# Beetech_NanoEvery.net
KiCad netlist of a schematic drawn in Altium Designer
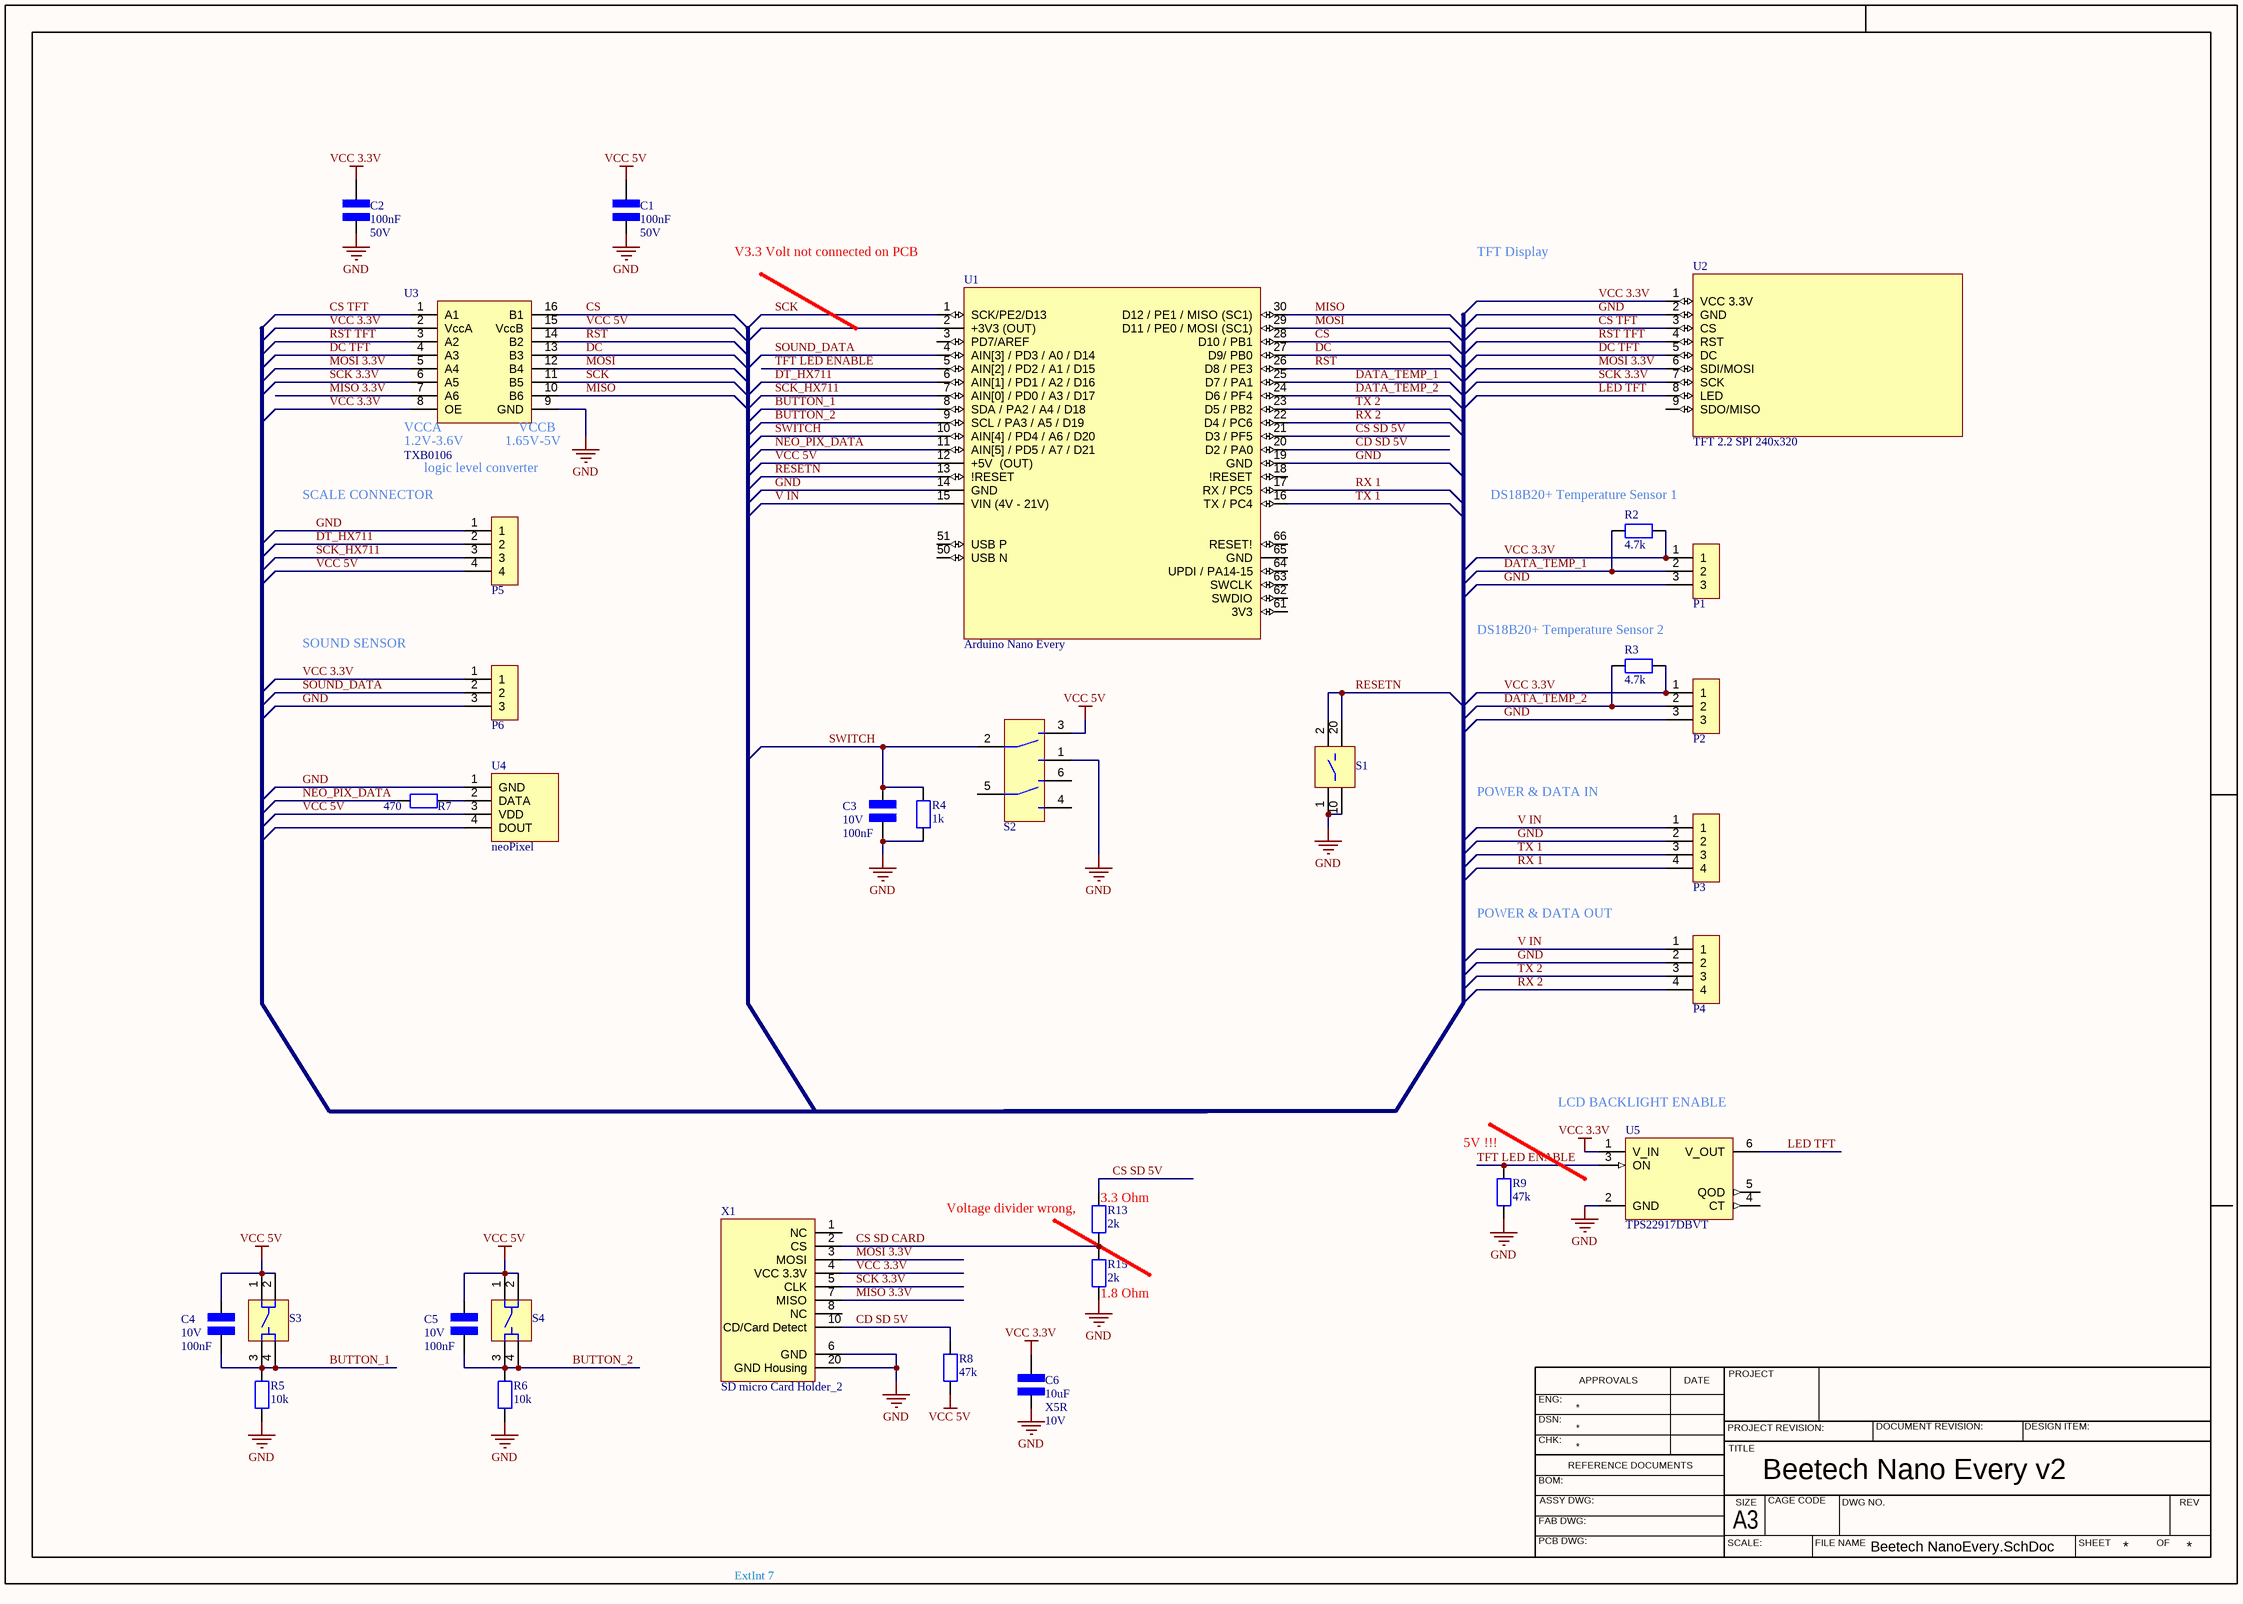
[diagram p0: Beetech NanoEvery.SchDoc]

(export (version "E")
  (design (tool "Eeschema 10.0.6"))
  (components
    (comp (ref "C1")
      (value "100nF")
      (footprint "CAP 0603")
      (description "C CERAMIC SMD")
      (fields (field (name "UMAX") "50V") (field (name "Comment") "100nF 0603_1"))
      (libsource (lib "Library CAP") (part "100nF 0603_1"))
    )
    (comp (ref "C2")
      (value "100nF")
      (footprint "CAP 0603")
      (description "C CERAMIC SMD")
      (fields (field (name "UMAX") "50V") (field (name "Comment") "100nF 0603_1"))
      (libsource (lib "Library CAP") (part "100nF 0603_1"))
    )
    (comp (ref "C3")
      (value "100nF")
      (footprint "CAP 0603")
      (description "C CERAMIC SMD")
      (fields (field (name "UMAX") "10V") (field (name "Comment") "100nF 0603"))
      (libsource (lib "Library CAP") (part "100nF 0603"))
    )
    (comp (ref "C4")
      (value "100nF")
      (footprint "CAP 0603")
      (description "C CERAMIC SMD")
      (fields (field (name "UMAX") "10V") (field (name "Comment") "100nF 0603"))
      (libsource (lib "Library CAP") (part "100nF 0603"))
    )
    (comp (ref "C5")
      (value "100nF")
      (footprint "CAP 0603")
      (description "C CERAMIC SMD")
      (fields (field (name "UMAX") "10V") (field (name "Comment") "100nF 0603"))
      (libsource (lib "Library CAP") (part "100nF 0603"))
    )
    (comp (ref "C6")
      (value "10uF")
      (footprint "CAP 0603")
      (description "C CERAMIC SMD")
      (fields
        (field (name "DIELEKTRIKUM") "X5R")
        (field (name "UMAX") "10V")
        (field (name "Comment") "10uF 0603")
      )
      (libsource (lib "Library CAP") (part "10uF 0603"))
    )
    (comp (ref "P1")
      (value "3-Pin Right Angle Housing")
      (footprint "3PIN - RND 205-EK254-2.54-03P")
      (description "3-Pin")
      (libsource (lib "Library Scematic") (part "3-Pin Screw Terminal"))
    )
    (comp (ref "P2")
      (value "3-Pin Right Angle Housing")
      (footprint "3PIN - RND 205-EK254-2.54-03P")
      (description "3-Pin")
      (libsource (lib "Library Scematic") (part "3-Pin Screw Terminal"))
    )
    (comp (ref "P3")
      (value "4-Pin Right Angle Housing")
      (footprint "4PIN - RND 205-EK254-2.54-04P")
      (description "4-Pin")
      (libsource (lib "Library Scematic") (part "4-Pin Screw Terminal"))
    )
    (comp (ref "P4")
      (value "4-Pin Right Angle Housing")
      (footprint "4PIN - RND 205-EK254-2.54-04P")
      (description "4-Pin")
      (libsource (lib "Library Scematic") (part "4-Pin Screw Terminal"))
    )
    (comp (ref "P5")
      (value "4-Pin Right Angle Housing")
      (footprint "4PIN - RND 205-EK254-2.54-04P")
      (description "4-Pin")
      (libsource (lib "Library Scematic") (part "4-Pin Screw Terminal"))
    )
    (comp (ref "P6")
      (value "3-Pin Right Angle Housing")
      (footprint "3PIN - RND 205-EK254-2.54-03P")
      (description "3-Pin")
      (libsource (lib "Library Scematic") (part "3-Pin Screw Terminal"))
    )
    (comp (ref "R2")
      (value "4.7k")
      (footprint "RES 0603 FOOTPRINT")
      (description "R SMD")
      (fields (field (name "Comment") "4.7k Ohm 0603"))
      (libsource (lib "Library RES") (part "4.7k Ohm 0603"))
    )
    (comp (ref "R3")
      (value "4.7k")
      (footprint "RES 0603 FOOTPRINT")
      (description "R SMD")
      (fields (field (name "Comment") "4.7k Ohm 0603"))
      (libsource (lib "Library RES") (part "4.7k Ohm 0603"))
    )
    (comp (ref "R4")
      (value "1k")
      (footprint "RES 0603 FOOTPRINT")
      (description "R SMD")
      (fields (field (name "Comment") "1k Ohm 0603"))
      (libsource (lib "Library RES") (part "1k Ohm 0603"))
    )
    (comp (ref "R5")
      (value "10k")
      (footprint "RES 0603 FOOTPRINT")
      (description "R SMD")
      (fields (field (name "Comment") "10k Ohm 0603"))
      (libsource (lib "Library RES") (part "10k Ohm 0603"))
    )
    (comp (ref "R6")
      (value "10k")
      (footprint "RES 0603 FOOTPRINT")
      (description "R SMD")
      (fields (field (name "Comment") "10k Ohm 0603"))
      (libsource (lib "Library RES") (part "10k Ohm 0603"))
    )
    (comp (ref "R7")
      (value "470")
      (footprint "RES 0603 FOOTPRINT")
      (description "R SMD")
      (fields (field (name "Comment") "470 Ohm 0603"))
      (libsource (lib "Library RES") (part "470 Ohm 0603"))
    )
    (comp (ref "R8")
      (value "47k")
      (footprint "RES 0603 FOOTPRINT")
      (description "R SMD")
      (fields (field (name "Comment") "47k Ohm 0603"))
      (libsource (lib "Library RES") (part "47k Ohm 0603"))
    )
    (comp (ref "R9")
      (value "47k")
      (footprint "RES 0402 FOOTPRINT")
      (description "R SMD")
      (fields (field (name "Comment") "47k Ohm 0402"))
      (libsource (lib "Library RES") (part "47k Ohm 0402"))
    )
    (comp (ref "R13")
      (value "2k")
      (footprint "RES 0603 FOOTPRINT")
      (description "R SMD")
      (fields (field (name "Comment") "2k Ohm 0603"))
      (libsource (lib "Library RES") (part "2k Ohm 0603"))
    )
    (comp (ref "R15")
      (value "2k")
      (footprint "RES 0603 FOOTPRINT")
      (description "R SMD")
      (fields (field (name "Comment") "2k Ohm 0603"))
      (libsource (lib "Library RES") (part "2k Ohm 0603"))
    )
    (comp (ref "S1")
      (value "Taster Print_SMD_2")
      (footprint "Taster Print - SMD - KMR241G LFS")
      (description "Taster")
      (libsource (lib "Library Scematic") (part "Taster Print_SMD_2"))
    )
    (comp (ref "S2")
      (value "Schiebeschalter EG2207")
      (footprint "Schiebeschalter on-on 2 P, EG2207")
      (description "Schiebeschalter on-on PCM12SMTR")
      (libsource (lib "Library Scematic") (part "Schiebeschalter EG2207"))
    )
    (comp (ref "S3")
      (value "Taster Print_SMD_3")
      (footprint "Taster Print - SMD - PTS647SM70SMTR2LFS")
      (description "Taster")
      (libsource (lib "Library Scematic") (part "Taster Print_SMD_6"))
    )
    (comp (ref "S4")
      (value "Taster Print_SMD_3")
      (footprint "Taster Print - SMD - PTS647SM70SMTR2LFS")
      (description "Taster")
      (libsource (lib "Library Scematic") (part "Taster Print_SMD_6"))
    )
    (comp (ref "U1")
      (value "Arduino Nano Every")
      (footprint "Arduino Nano Every")
      (description "https://store.arduino.cc/nano-every-pack")
      (libsource (lib "Library Scematic") (part "Arduino Nano Every"))
    )
    (comp (ref "U2")
      (value "TFT 2.2 SPI 240x320")
      (footprint "TFT 2.2 SPI 240x320")
      (libsource (lib "Library Scematic") (part "TFT 2.2 SPI 240x320"))
    )
    (comp (ref "U3")
      (value "TXB0106")
      (footprint "TSSOP-16L")
      (description "Level Converter TXB0106")
      (libsource (lib "Library Scematic") (part "TXB0106 Level Converter"))
    )
    (comp (ref "U4")
      (value "neoPixel")
      (footprint "neoPixel 5050 adafruit 1655")
      (description "neoPixel 5050 adafruit 1655")
      (libsource (lib "Library Scematic") (part "neoPixel 5050 adafruit 1655"))
    )
    (comp (ref "U5")
      (value "TPS22917DBVT")
      (footprint "SOT23 - 6")
      (description "High Side Switch")
      (libsource (lib "Library Scematic") (part "TPS22917DBVT"))
    )
    (comp (ref "X1")
      (value "SD micro Card Holder_2")
      (footprint "SD Card Holder - micro - 2 - sd Card inserted")
      (description "SD micro Card  Holder")
      (libsource (lib "Library Scematic") (part "SD micro Card Holder_2"))
    )
  )
  (nets
    (net (code "1") (name "/BUTTON_1") (class "Default")
      (node (ref "C4") (pin "2") (pinfunction "2_2") (pintype "passive"))
      (node (ref "R5") (pin "2") (pinfunction "2_2") (pintype "passive"))
      (node (ref "S3") (pin "3") (pinfunction "3_3") (pintype "passive"))
      (node (ref "S3") (pin "4") (pinfunction "4_4") (pintype "passive"))
      (node (ref "U1") (pin "8") (pinfunction "SDA_/_PA2_/_A4_/_D18_8") (pintype "bidirectional"))
    )
    (net (code "2") (name "/BUTTON_2") (class "Default")
      (node (ref "C5") (pin "2") (pinfunction "2_2") (pintype "passive"))
      (node (ref "R6") (pin "2") (pinfunction "2_2") (pintype "passive"))
      (node (ref "S4") (pin "3") (pinfunction "3_3") (pintype "passive"))
      (node (ref "S4") (pin "4") (pinfunction "4_4") (pintype "passive"))
      (node (ref "U1") (pin "9") (pinfunction "SCL_/_PA3_/_A5_/_D19_9") (pintype "bidirectional"))
    )
    (net (code "3") (name "/CD SD 5V") (class "Default")
      (node (ref "R8") (pin "1") (pinfunction "1_1") (pintype "passive"))
      (node (ref "U1") (pin "20") (pinfunction "D2_/_PA0_20") (pintype "bidirectional"))
      (node (ref "X1") (pin "10") (pinfunction "CD/Card_Detect_10") (pintype "passive"))
    )
    (net (code "4") (name "/CS") (class "Default")
      (node (ref "U1") (pin "28") (pinfunction "D10_/_PB1_28") (pintype "bidirectional"))
      (node (ref "U3") (pin "16") (pinfunction "B1_16") (pintype "passive"))
    )
    (net (code "5") (name "/CS SD 5V") (class "Default")
      (node (ref "R13") (pin "2") (pinfunction "2_2") (pintype "passive"))
      (node (ref "U1") (pin "21") (pinfunction "D3_/_PF5_21") (pintype "bidirectional"))
    )
    (net (code "6") (name "/CS SD CARD") (class "Default")
      (node (ref "R13") (pin "1") (pinfunction "1_1") (pintype "passive"))
      (node (ref "R15") (pin "2") (pinfunction "2_2") (pintype "passive"))
      (node (ref "X1") (pin "2") (pinfunction "CS_2") (pintype "passive"))
    )
    (net (code "7") (name "/CS TFT") (class "Default")
      (node (ref "U2") (pin "3") (pinfunction "CS_3") (pintype "bidirectional"))
      (node (ref "U3") (pin "1") (pinfunction "A1_1") (pintype "power_in"))
    )
    (net (code "8") (name "/DATA_TEMP_1") (class "Default")
      (node (ref "P1") (pin "2") (pinfunction "2_2") (pintype "passive"))
      (node (ref "R2") (pin "2") (pinfunction "2_2") (pintype "passive"))
      (node (ref "U1") (pin "25") (pinfunction "D7_/_PA1_25") (pintype "bidirectional"))
    )
    (net (code "9") (name "/DATA_TEMP_2") (class "Default")
      (node (ref "P2") (pin "2") (pinfunction "2_2") (pintype "passive"))
      (node (ref "R3") (pin "2") (pinfunction "2_2") (pintype "passive"))
      (node (ref "U1") (pin "24") (pinfunction "D6_/_PF4_24") (pintype "bidirectional"))
    )
    (net (code "10") (name "/DC") (class "Default")
      (node (ref "U1") (pin "27") (pinfunction "D9/_PB0_27") (pintype "bidirectional"))
      (node (ref "U3") (pin "13") (pinfunction "B3_13") (pintype "passive"))
    )
    (net (code "11") (name "/DC TFT") (class "Default")
      (node (ref "U2") (pin "5") (pinfunction "DC_5") (pintype "bidirectional"))
      (node (ref "U3") (pin "4") (pinfunction "A3_4") (pintype "passive"))
    )
    (net (code "12") (name "/DT_HX711") (class "Default")
      (node (ref "P5") (pin "2") (pinfunction "2_2") (pintype "passive"))
      (node (ref "U1") (pin "6") (pinfunction "AIN[1]_/_PD1_/_A2_/_D16_6") (pintype "bidirectional"))
    )
    (net (code "13") (name "/LED TFT") (class "Default")
      (node (ref "U2") (pin "8") (pinfunction "LED_8") (pintype "bidirectional"))
      (node (ref "U5") (pin "6") (pinfunction "V_OUT_6") (pintype "power_in"))
    )
    (net (code "14") (name "/MISO") (class "Default")
      (node (ref "U1") (pin "30") (pinfunction "D12_/_PE1_/_MISO_(SC1)_30") (pintype "bidirectional"))
      (node (ref "U3") (pin "10") (pinfunction "B6_10") (pintype "passive"))
    )
    (net (code "15") (name "/MISO 3.3V") (class "Default")
      (node (ref "U3") (pin "7") (pinfunction "A6_7") (pintype "passive"))
      (node (ref "X1") (pin "7") (pinfunction "MISO_7") (pintype "passive"))
    )
    (net (code "16") (name "/MOSI") (class "Default")
      (node (ref "U1") (pin "29") (pinfunction "D11_/_PE0_/_MOSI_(SC1)_29") (pintype "bidirectional"))
      (node (ref "U3") (pin "12") (pinfunction "B4_12") (pintype "passive"))
    )
    (net (code "17") (name "/MOSI 3.3V") (class "Default")
      (node (ref "U2") (pin "6") (pinfunction "SDI/MOSI_6") (pintype "bidirectional"))
      (node (ref "U3") (pin "5") (pinfunction "A4_5") (pintype "passive"))
      (node (ref "X1") (pin "3") (pinfunction "MOSI_3") (pintype "passive"))
    )
    (net (code "18") (name "/NEO_PIX_DATA") (class "Default")
      (node (ref "R7") (pin "1") (pinfunction "1_1") (pintype "passive"))
      (node (ref "U1") (pin "11") (pinfunction "AIN[5]_/_PD5_/_A7_/_D21_11") (pintype "bidirectional"))
    )
    (net (code "19") (name "/RESETN") (class "Default")
      (node (ref "S1") (pin "2") (pinfunction "2_2") (pintype "passive"))
      (node (ref "S1") (pin "20") (pinfunction "20_20") (pintype "passive"))
      (node (ref "U1") (pin "13") (pinfunction "!RESET_13") (pintype "bidirectional"))
    )
    (net (code "20") (name "/RST") (class "Default")
      (node (ref "U1") (pin "26") (pinfunction "D8_/_PE3_26") (pintype "bidirectional"))
      (node (ref "U3") (pin "14") (pinfunction "B2_14") (pintype "passive"))
    )
    (net (code "21") (name "/RST TFT") (class "Default")
      (node (ref "U2") (pin "4") (pinfunction "RST_4") (pintype "bidirectional"))
      (node (ref "U3") (pin "3") (pinfunction "A2_3") (pintype "passive"))
    )
    (net (code "22") (name "/RX 1") (class "Default")
      (node (ref "P3") (pin "4") (pinfunction "4_4") (pintype "passive"))
      (node (ref "U1") (pin "17") (pinfunction "RX_/_PC5_17") (pintype "bidirectional"))
    )
    (net (code "23") (name "/RX 2") (class "Default")
      (node (ref "P4") (pin "4") (pinfunction "4_4") (pintype "passive"))
      (node (ref "U1") (pin "22") (pinfunction "D4_/_PC6_22") (pintype "bidirectional"))
    )
    (net (code "24") (name "/SCK") (class "Default")
      (node (ref "U1") (pin "1") (pinfunction "SCK/PE2/D13_1") (pintype "bidirectional"))
      (node (ref "U3") (pin "11") (pinfunction "B5_11") (pintype "passive"))
    )
    (net (code "25") (name "/SCK 3.3V") (class "Default")
      (node (ref "U2") (pin "7") (pinfunction "SCK_7") (pintype "bidirectional"))
      (node (ref "U3") (pin "6") (pinfunction "A5_6") (pintype "passive"))
      (node (ref "X1") (pin "5") (pinfunction "CLK_5") (pintype "passive"))
    )
    (net (code "26") (name "/SCK_HX711") (class "Default")
      (node (ref "P5") (pin "3") (pinfunction "3_3") (pintype "passive"))
      (node (ref "U1") (pin "7") (pinfunction "AIN[0]_/_PD0_/_A3_/_D17_7") (pintype "bidirectional"))
    )
    (net (code "27") (name "/SOUND_DATA") (class "Default")
      (node (ref "P6") (pin "2") (pinfunction "2_2") (pintype "passive"))
      (node (ref "U1") (pin "4") (pinfunction "AIN[3]_/_PD3_/_A0_/_D14_4") (pintype "bidirectional"))
    )
    (net (code "28") (name "/SWITCH") (class "Default")
      (node (ref "C3") (pin "1") (pinfunction "1_1") (pintype "passive"))
      (node (ref "R4") (pin "2") (pinfunction "2_2") (pintype "passive"))
      (node (ref "S2") (pin "2") (pinfunction "2_2") (pintype "passive"))
      (node (ref "U1") (pin "10") (pinfunction "AIN[4]_/_PD4_/_A6_/_D20_10") (pintype "bidirectional"))
    )
    (net (code "29") (name "/TFT LED ENABLE") (class "Default")
      (node (ref "R9") (pin "2") (pinfunction "2_2") (pintype "passive"))
      (node (ref "U1") (pin "5") (pinfunction "AIN[2]_/_PD2_/_A1_/_D15_5") (pintype "bidirectional"))
      (node (ref "U5") (pin "3") (pinfunction "ON_3") (pintype "input"))
    )
    (net (code "30") (name "/TX 1") (class "Default")
      (node (ref "P3") (pin "3") (pinfunction "3_3") (pintype "passive"))
      (node (ref "U1") (pin "16") (pinfunction "TX_/_PC4_16") (pintype "bidirectional"))
    )
    (net (code "31") (name "/TX 2") (class "Default")
      (node (ref "P4") (pin "3") (pinfunction "3_3") (pintype "passive"))
      (node (ref "U1") (pin "23") (pinfunction "D5_/_PB2_23") (pintype "bidirectional"))
    )
    (net (code "32") (name "/V IN") (class "Default")
      (node (ref "P3") (pin "1") (pinfunction "1_1") (pintype "passive"))
      (node (ref "P4") (pin "1") (pinfunction "1_1") (pintype "passive"))
      (node (ref "U1") (pin "15") (pinfunction "VIN_(4V_-_21V)_15") (pintype "power_in"))
    )
    (net (code "33") (name "GND") (class "Default")
      (node (ref "C1") (pin "1") (pinfunction "1_1") (pintype "passive"))
      (node (ref "C2") (pin "1") (pinfunction "1_1") (pintype "passive"))
      (node (ref "C3") (pin "2") (pinfunction "2_2") (pintype "passive"))
      (node (ref "C6") (pin "1") (pinfunction "1_1") (pintype "passive"))
      (node (ref "P1") (pin "3") (pinfunction "3_3") (pintype "passive"))
      (node (ref "P2") (pin "3") (pinfunction "3_3") (pintype "passive"))
      (node (ref "P3") (pin "2") (pinfunction "2_2") (pintype "passive"))
      (node (ref "P4") (pin "2") (pinfunction "2_2") (pintype "passive"))
      (node (ref "P5") (pin "1") (pinfunction "1_1") (pintype "passive"))
      (node (ref "P6") (pin "3") (pinfunction "3_3") (pintype "passive"))
      (node (ref "R15") (pin "1") (pinfunction "1_1") (pintype "passive"))
      (node (ref "R4") (pin "1") (pinfunction "1_1") (pintype "passive"))
      (node (ref "R5") (pin "1") (pinfunction "1_1") (pintype "passive"))
      (node (ref "R6") (pin "1") (pinfunction "1_1") (pintype "passive"))
      (node (ref "R9") (pin "1") (pinfunction "1_1") (pintype "passive"))
      (node (ref "S1") (pin "1") (pinfunction "1_1") (pintype "passive"))
      (node (ref "S1") (pin "10") (pinfunction "10_10") (pintype "passive"))
      (node (ref "S2") (pin "1") (pinfunction "1_1") (pintype "passive"))
      (node (ref "U1") (pin "14") (pinfunction "GND_14") (pintype "power_in"))
      (node (ref "U1") (pin "19") (pinfunction "GND_19") (pintype "bidirectional"))
      (node (ref "U2") (pin "2") (pinfunction "GND_2") (pintype "bidirectional"))
      (node (ref "U3") (pin "9") (pinfunction "GND_9") (pintype "passive"))
      (node (ref "U4") (pin "1") (pinfunction "GND_1") (pintype "passive"))
      (node (ref "U5") (pin "2") (pinfunction "GND_2") (pintype "power_in"))
      (node (ref "X1") (pin "20") (pinfunction "GND_Housing_20") (pintype "passive"))
      (node (ref "X1") (pin "6") (pinfunction "GND_6") (pintype "passive"))
    )
    (net (code "34") (name "Net-(U4-DATA)") (class "Default")
      (node (ref "R7") (pin "2") (pinfunction "2_2") (pintype "passive"))
      (node (ref "U4") (pin "2") (pinfunction "DATA_2") (pintype "passive"))
    )
    (net (code "35") (name "VCC 3.3V") (class "Default")
      (node (ref "C2") (pin "2") (pinfunction "2_2") (pintype "passive"))
      (node (ref "C6") (pin "2") (pinfunction "2_2") (pintype "passive"))
      (node (ref "P1") (pin "1") (pinfunction "1_1") (pintype "passive"))
      (node (ref "P2") (pin "1") (pinfunction "1_1") (pintype "passive"))
      (node (ref "P6") (pin "1") (pinfunction "1_1") (pintype "passive"))
      (node (ref "R2") (pin "1") (pinfunction "1_1") (pintype "passive"))
      (node (ref "R3") (pin "1") (pinfunction "1_1") (pintype "passive"))
      (node (ref "U2") (pin "1") (pinfunction "VCC_3.3V_1") (pintype "bidirectional"))
      (node (ref "U3") (pin "2") (pinfunction "VccA_2") (pintype "passive"))
      (node (ref "U3") (pin "8") (pinfunction "OE_8") (pintype "passive"))
      (node (ref "U5") (pin "1") (pinfunction "V_IN_1") (pintype "power_in"))
      (node (ref "X1") (pin "4") (pinfunction "VCC_3.3V_4") (pintype "passive"))
    )
    (net (code "36") (name "VCC 5V") (class "Default")
      (node (ref "C1") (pin "2") (pinfunction "2_2") (pintype "passive"))
      (node (ref "C4") (pin "1") (pinfunction "1_1") (pintype "passive"))
      (node (ref "C5") (pin "1") (pinfunction "1_1") (pintype "passive"))
      (node (ref "P5") (pin "4") (pinfunction "4_4") (pintype "passive"))
      (node (ref "R8") (pin "2") (pinfunction "2_2") (pintype "passive"))
      (node (ref "S2") (pin "3") (pinfunction "3_3") (pintype "passive"))
      (node (ref "S3") (pin "1") (pinfunction "1_1") (pintype "passive"))
      (node (ref "S3") (pin "2") (pinfunction "2_2") (pintype "passive"))
      (node (ref "S4") (pin "1") (pinfunction "1_1") (pintype "passive"))
      (node (ref "S4") (pin "2") (pinfunction "2_2") (pintype "passive"))
      (node (ref "U1") (pin "12") (pinfunction "+5V__(OUT)_12") (pintype "power_in"))
      (node (ref "U3") (pin "15") (pinfunction "VccB_15") (pintype "passive"))
      (node (ref "U4") (pin "3") (pinfunction "VDD_3") (pintype "passive"))
    )
    (net (code "37") (name "unconnected-(S2-Pad4)") (class "Default")
      (node (ref "S2") (pin "4") (pinfunction "4_4") (pintype "passive"))
    )
    (net (code "38") (name "unconnected-(S2-Pad5)") (class "Default")
      (node (ref "S2") (pin "5") (pinfunction "5_5") (pintype "passive"))
    )
    (net (code "39") (name "unconnected-(S2-Pad6)") (class "Default")
      (node (ref "S2") (pin "6") (pinfunction "6_6") (pintype "passive"))
    )
    (net (code "40") (name "unconnected-(U1-!RESET-Pad18)") (class "Default")
      (node (ref "U1") (pin "18") (pinfunction "!RESET_18") (pintype "bidirectional"))
    )
    (net (code "41") (name "unconnected-(U1-+3V3_(OUT)-Pad2)") (class "Default")
      (node (ref "U1") (pin "2") (pinfunction "+3V3_(OUT)_2") (pintype "power_in"))
    )
    (net (code "42") (name "unconnected-(U1-3V3-Pad61)") (class "Default")
      (node (ref "U1") (pin "61") (pinfunction "3V3_61") (pintype "bidirectional"))
    )
    (net (code "43") (name "unconnected-(U1-GND-Pad65)") (class "Default")
      (node (ref "U1") (pin "65") (pinfunction "GND_65") (pintype "power_in"))
    )
    (net (code "44") (name "unconnected-(U1-PD7{slash}AREF-Pad3)") (class "Default")
      (node (ref "U1") (pin "3") (pinfunction "PD7/AREF_3") (pintype "bidirectional"))
    )
    (net (code "45") (name "unconnected-(U1-RESET!-Pad66)") (class "Default")
      (node (ref "U1") (pin "66") (pinfunction "RESET!_66") (pintype "bidirectional"))
    )
    (net (code "46") (name "unconnected-(U1-SWCLK-Pad63)") (class "Default")
      (node (ref "U1") (pin "63") (pinfunction "SWCLK_63") (pintype "bidirectional"))
    )
    (net (code "47") (name "unconnected-(U1-SWDIO-Pad62)") (class "Default")
      (node (ref "U1") (pin "62") (pinfunction "SWDIO_62") (pintype "bidirectional"))
    )
    (net (code "48") (name "unconnected-(U1-UPDI_{slash}_PA14-15-Pad64)") (class "Default")
      (node (ref "U1") (pin "64") (pinfunction "UPDI_/_PA14-15_64") (pintype "bidirectional"))
    )
    (net (code "49") (name "unconnected-(U1-USB_N-Pad50)") (class "Default")
      (node (ref "U1") (pin "50") (pinfunction "USB_N_50") (pintype "bidirectional"))
    )
    (net (code "50") (name "unconnected-(U1-USB_P-Pad51)") (class "Default")
      (node (ref "U1") (pin "51") (pinfunction "USB_P_51") (pintype "bidirectional"))
    )
    (net (code "51") (name "unconnected-(U2-SDO{slash}MISO-Pad9)") (class "Default")
      (node (ref "U2") (pin "9") (pinfunction "SDO/MISO_9") (pintype "bidirectional"))
    )
    (net (code "52") (name "unconnected-(U4-DOUT-Pad4)") (class "Default")
      (node (ref "U4") (pin "4") (pinfunction "DOUT_4") (pintype "passive"))
    )
    (net (code "53") (name "unconnected-(U5-CT-Pad4)") (class "Default")
      (node (ref "U5") (pin "4") (pinfunction "CT_4") (pintype "output"))
    )
    (net (code "54") (name "unconnected-(U5-QOD-Pad5)") (class "Default")
      (node (ref "U5") (pin "5") (pinfunction "QOD_5") (pintype "output"))
    )
    (net (code "55") (name "unconnected-(X1-NC-Pad1)") (class "Default")
      (node (ref "X1") (pin "1") (pinfunction "NC_1") (pintype "passive"))
    )
    (net (code "56") (name "unconnected-(X1-NC-Pad8)") (class "Default")
      (node (ref "X1") (pin "8") (pinfunction "NC_8") (pintype "passive"))
    )
  )
)
